# Sheet1.net
KiCad netlist of a schematic drawn in Altium Designer
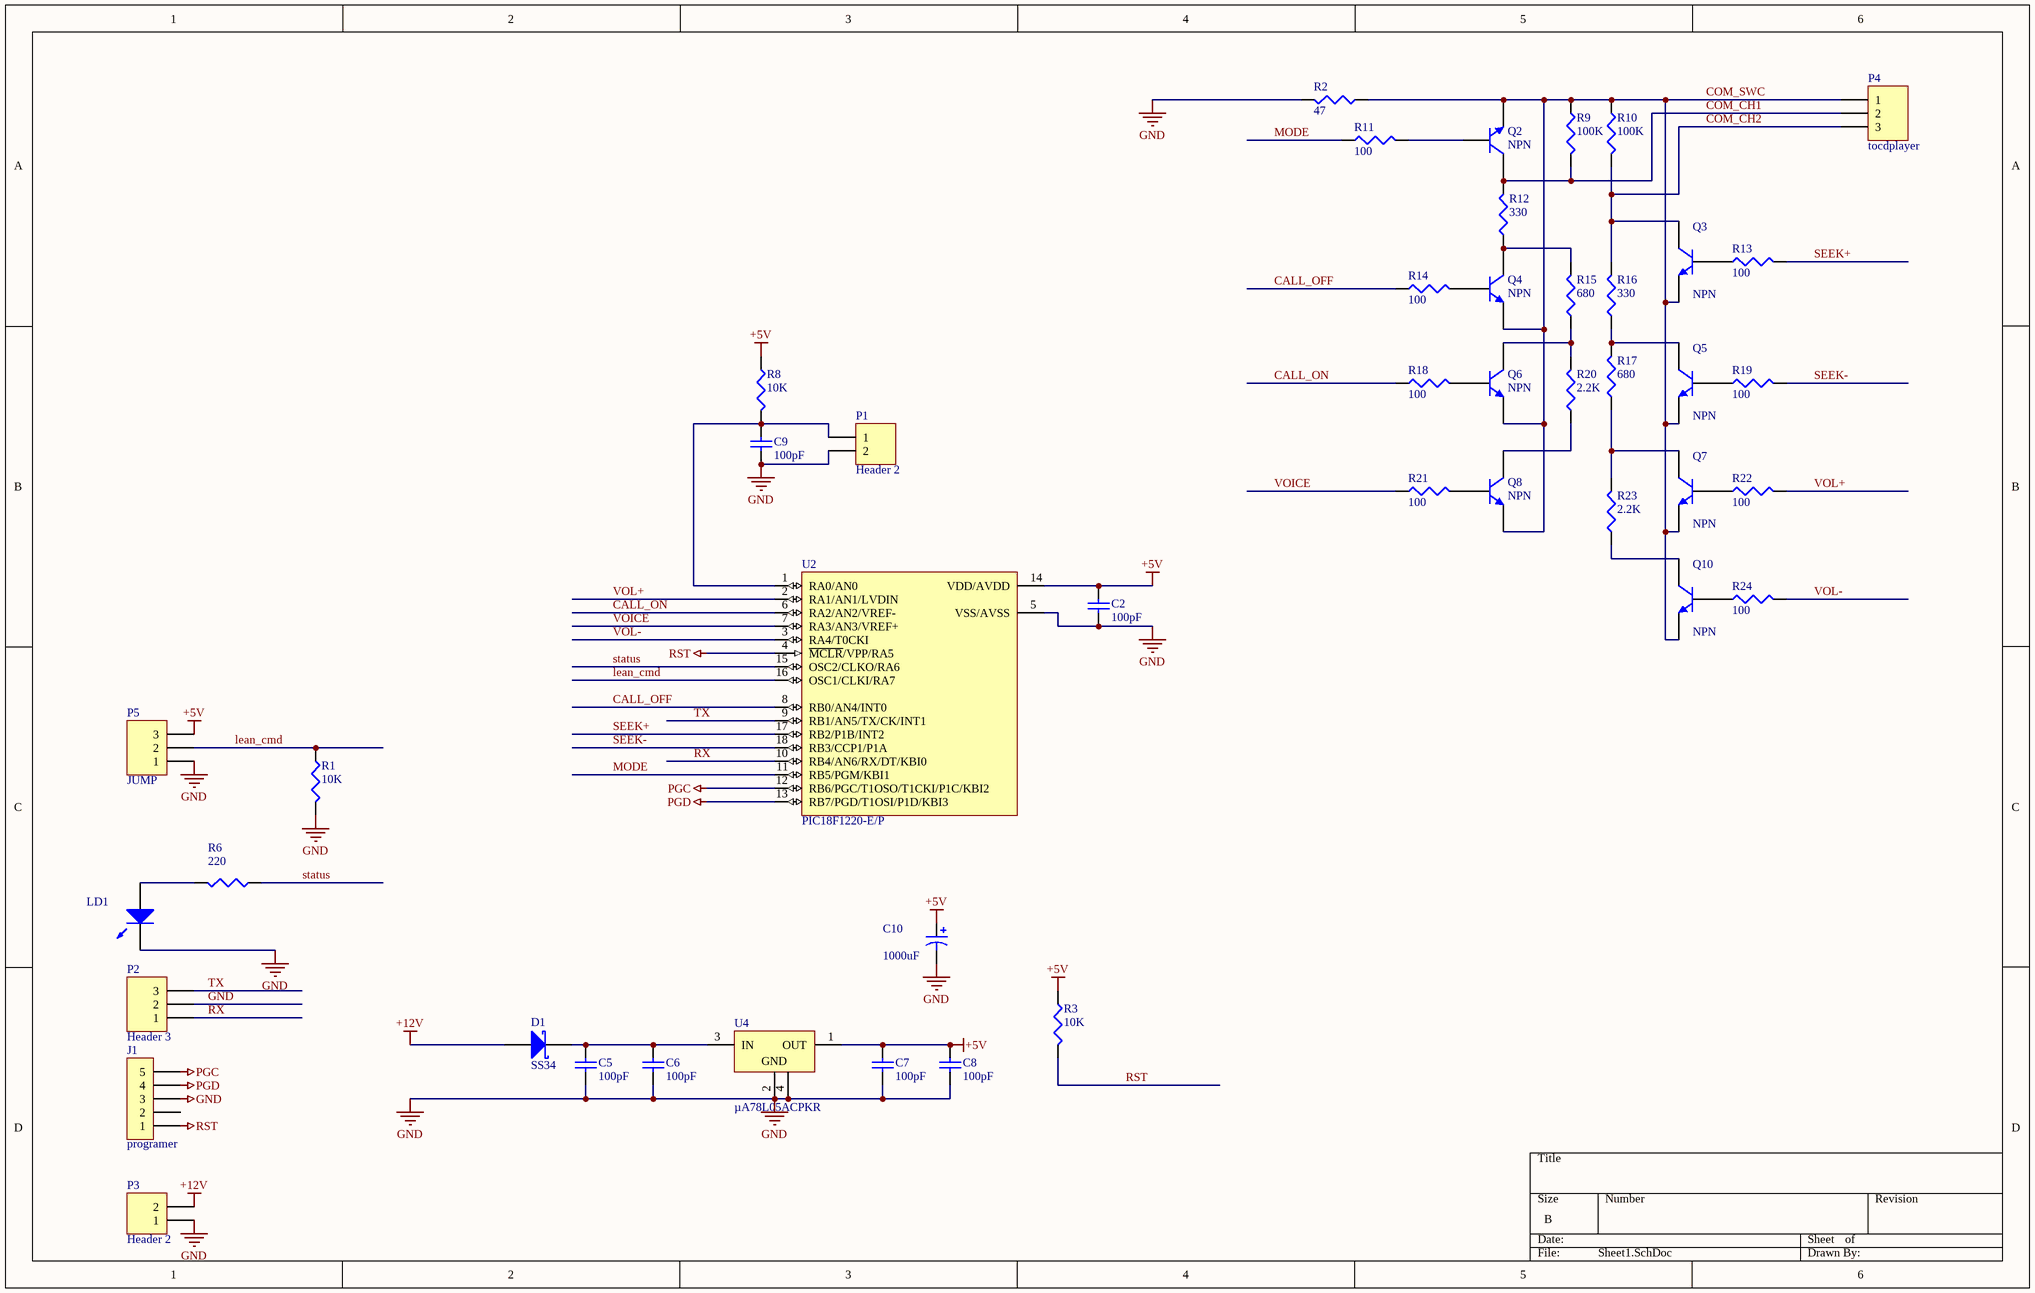
[diagram p0: Sheet1.SchDoc]

(export (version "E")
  (design (tool "Eeschema 10.0.6"))
  (components
    (comp (ref "C2")
      (value "100pF")
      (footprint "RESC2012L")
      (description "Capacitor (Semiconductor SIM Model)")
      (fields (field (name "Comment") "Cap Semi") (field (name "PUBLISHER") "Altium Limited"))
      (libsource (lib "Miscellaneous Devices") (part "Cap Semi"))
    )
    (comp (ref "C5")
      (value "100pF")
      (footprint "RESC2012L")
      (description "Capacitor (Semiconductor SIM Model)")
      (fields (field (name "Comment") "Cap Semi") (field (name "PUBLISHER") "Altium Limited"))
      (libsource (lib "Miscellaneous Devices") (part "Cap Semi"))
    )
    (comp (ref "C6")
      (value "100pF")
      (footprint "RESC2012L")
      (description "Capacitor (Semiconductor SIM Model)")
      (fields (field (name "Comment") "Cap Semi") (field (name "PUBLISHER") "Altium Limited"))
      (libsource (lib "Miscellaneous Devices") (part "Cap Semi"))
    )
    (comp (ref "C7")
      (value "100pF")
      (footprint "RESC2012L")
      (description "Capacitor (Semiconductor SIM Model)")
      (fields (field (name "Comment") "Cap Semi") (field (name "PUBLISHER") "Altium Limited"))
      (libsource (lib "Miscellaneous Devices") (part "Cap Semi"))
    )
    (comp (ref "C8")
      (value "100pF")
      (footprint "RESC2012L")
      (description "Capacitor (Semiconductor SIM Model)")
      (fields (field (name "Comment") "Cap Semi") (field (name "PUBLISHER") "Altium Limited"))
      (libsource (lib "Miscellaneous Devices") (part "Cap Semi"))
    )
    (comp (ref "C9")
      (value "100pF")
      (footprint "RESC2012L")
      (description "Capacitor (Semiconductor SIM Model)")
      (fields (field (name "Comment") "Cap Semi") (field (name "PUBLISHER") "Altium Limited"))
      (libsource (lib "Miscellaneous Devices") (part "Cap Semi"))
    )
    (comp (ref "C10")
      (value "1000uF")
      (footprint "CAP8x8")
      (description "CAP ALUM 1000UF 10V 20% SMD")
      (fields (field (name "Comment") "EEE-FT1A102AP") (field (name "PUBLISHER") "Altium Limited"))
      (libsource (lib "Miscellaneous Devices") (part "Cap Pol1"))
    )
    (comp (ref "D1")
      (value "SS34")
      (footprint "SMB")
      (description "DIODE SCHOTTKY 40V 3A SMC")
      (fields (field (name "PUBLISHER") "Altium Limited"))
      (libsource (lib "Schlib1") (part "D Schottky SS34"))
    )
    (comp (ref "J1")
      (value "programer")
      (footprint "HDR1x5")
      (description "Connector")
      (libsource (lib "*") (part "CON5"))
    )
    (comp (ref "LD1")
      (value "LNJ911W8BRU")
      (footprint "CD3216-1206")
      (description "LED BLUE THRU BOARD 1206")
      (libsource (lib "AM335X_ZCZ") (part "LEDRED1206"))
    )
    (comp (ref "P1")
      (value "Header 2")
      (footprint "CON_PLUG2")
      (description "Header, 2-Pin")
      (fields (field (name "PUBLISHER") "Altium Limited"))
      (libsource (lib "Miscellaneous Connectors") (part "Header 2"))
    )
    (comp (ref "P2")
      (value "Header 3")
      (footprint "HDR1X3")
      (description "Header, 3-Pin")
      (fields (field (name "PUBLISHER") "Altium Limited"))
      (libsource (lib "Miscellaneous Connectors") (part "Header 3"))
    )
    (comp (ref "P3")
      (value "Header 2")
      (footprint "HDR1X2")
      (description "Header, 2-Pin")
      (fields (field (name "PUBLISHER") "Altium Limited"))
      (libsource (lib "") (part "Header 2_1"))
    )
    (comp (ref "P4")
      (value "tocdplayer")
      (footprint "HDR1X3")
      (description "Header, 3-Pin")
      (fields (field (name "PUBLISHER") "Altium Limited"))
      (libsource (lib "") (part "Header 3_1"))
    )
    (comp (ref "P5")
      (value "JUMP")
      (footprint "HDR1X3")
      (description "Header, 3-Pin")
      (fields (field (name "PUBLISHER") "Altium Limited"))
      (libsource (lib "Miscellaneous Connectors") (part "Header 3"))
    )
    (comp (ref "Q2")
      (value "NPN")
      (footprint "SOT-23B")
      (description "NPN Bipolar Transistor")
      (fields (field (name "PUBLISHER") "Altium Limited"))
      (libsource (lib "Miscellaneous Devices") (part "NPN"))
    )
    (comp (ref "Q3")
      (value "NPN")
      (footprint "SOT-23B")
      (description "NPN Bipolar Transistor")
      (fields (field (name "PUBLISHER") "Altium Limited"))
      (libsource (lib "Miscellaneous Devices") (part "NPN"))
    )
    (comp (ref "Q4")
      (value "NPN")
      (footprint "SOT-23B")
      (description "NPN Bipolar Transistor")
      (fields (field (name "PUBLISHER") "Altium Limited"))
      (libsource (lib "Miscellaneous Devices") (part "NPN"))
    )
    (comp (ref "Q5")
      (value "NPN")
      (footprint "SOT-23B")
      (description "NPN Bipolar Transistor")
      (fields (field (name "PUBLISHER") "Altium Limited"))
      (libsource (lib "Miscellaneous Devices") (part "NPN"))
    )
    (comp (ref "Q6")
      (value "NPN")
      (footprint "SOT-23B")
      (description "NPN Bipolar Transistor")
      (fields (field (name "PUBLISHER") "Altium Limited"))
      (libsource (lib "Miscellaneous Devices") (part "NPN"))
    )
    (comp (ref "Q7")
      (value "NPN")
      (footprint "SOT-23B")
      (description "NPN Bipolar Transistor")
      (fields (field (name "PUBLISHER") "Altium Limited"))
      (libsource (lib "Miscellaneous Devices") (part "NPN"))
    )
    (comp (ref "Q8")
      (value "NPN")
      (footprint "SOT-23B")
      (description "NPN Bipolar Transistor")
      (fields (field (name "PUBLISHER") "Altium Limited"))
      (libsource (lib "Miscellaneous Devices") (part "NPN"))
    )
    (comp (ref "Q10")
      (value "NPN")
      (footprint "SOT-23B")
      (description "NPN Bipolar Transistor")
      (fields (field (name "PUBLISHER") "Altium Limited"))
      (libsource (lib "Miscellaneous Devices") (part "NPN"))
    )
    (comp (ref "R1")
      (value "10K")
      (footprint "RESC2012L")
      (description "Resistor")
      (fields (field (name "Comment") "Res3") (field (name "PUBLISHER") "Altium Limited"))
      (libsource (lib "Miscellaneous Devices") (part "Res3"))
    )
    (comp (ref "R2")
      (value "47")
      (footprint "RESC2012L")
      (description "Resistor")
      (fields (field (name "Comment") "Res3") (field (name "PUBLISHER") "Altium Limited"))
      (libsource (lib "Miscellaneous Devices") (part "Res3"))
    )
    (comp (ref "R3")
      (value "10K")
      (footprint "RESC2012L")
      (description "Resistor")
      (fields (field (name "Comment") "Res3") (field (name "PUBLISHER") "Altium Limited"))
      (libsource (lib "Miscellaneous Devices") (part "Res3"))
    )
    (comp (ref "R6")
      (value "220")
      (footprint "RESC2012L")
      (description "Resistor")
      (fields (field (name "Comment") "Res3") (field (name "PUBLISHER") "Altium Limited"))
      (libsource (lib "Miscellaneous Devices") (part "Res3"))
    )
    (comp (ref "R8")
      (value "10K")
      (footprint "RESC2012L")
      (description "Resistor")
      (fields (field (name "Comment") "Res3") (field (name "PUBLISHER") "Altium Limited"))
      (libsource (lib "Miscellaneous Devices") (part "Res3"))
    )
    (comp (ref "R9")
      (value "100K")
      (footprint "RESC2012L")
      (description "Resistor")
      (fields (field (name "Comment") "Res3") (field (name "PUBLISHER") "Altium Limited"))
      (libsource (lib "Miscellaneous Devices") (part "Res3"))
    )
    (comp (ref "R10")
      (value "100K")
      (footprint "RESC2012L")
      (description "Resistor")
      (fields (field (name "Comment") "Res3") (field (name "PUBLISHER") "Altium Limited"))
      (libsource (lib "Miscellaneous Devices") (part "Res3"))
    )
    (comp (ref "R11")
      (value "100")
      (footprint "RESC2012L")
      (description "Resistor")
      (fields (field (name "Comment") "Res3") (field (name "PUBLISHER") "Altium Limited"))
      (libsource (lib "Miscellaneous Devices") (part "Res3"))
    )
    (comp (ref "R12")
      (value "330")
      (footprint "RESC2012L")
      (description "Resistor")
      (fields (field (name "Comment") "Res3") (field (name "PUBLISHER") "Altium Limited"))
      (libsource (lib "Miscellaneous Devices") (part "Res3"))
    )
    (comp (ref "R13")
      (value "100")
      (footprint "RESC2012L")
      (description "Resistor")
      (fields (field (name "Comment") "Res3") (field (name "PUBLISHER") "Altium Limited"))
      (libsource (lib "Miscellaneous Devices") (part "Res3"))
    )
    (comp (ref "R14")
      (value "100")
      (footprint "RESC2012L")
      (description "Resistor")
      (fields (field (name "Comment") "Res3") (field (name "PUBLISHER") "Altium Limited"))
      (libsource (lib "Miscellaneous Devices") (part "Res3"))
    )
    (comp (ref "R15")
      (value "680")
      (footprint "RESC2012L")
      (description "Resistor")
      (fields (field (name "Comment") "Res3") (field (name "PUBLISHER") "Altium Limited"))
      (libsource (lib "Miscellaneous Devices") (part "Res3"))
    )
    (comp (ref "R16")
      (value "330")
      (footprint "RESC2012L")
      (description "Resistor")
      (fields (field (name "Comment") "Res3") (field (name "PUBLISHER") "Altium Limited"))
      (libsource (lib "Miscellaneous Devices") (part "Res3"))
    )
    (comp (ref "R17")
      (value "680")
      (footprint "RESC2012L")
      (description "Resistor")
      (fields (field (name "Comment") "Res3") (field (name "PUBLISHER") "Altium Limited"))
      (libsource (lib "Miscellaneous Devices") (part "Res3"))
    )
    (comp (ref "R18")
      (value "100")
      (footprint "RESC2012L")
      (description "Resistor")
      (fields (field (name "Comment") "Res3") (field (name "PUBLISHER") "Altium Limited"))
      (libsource (lib "Miscellaneous Devices") (part "Res3"))
    )
    (comp (ref "R19")
      (value "100")
      (footprint "RESC2012L")
      (description "Resistor")
      (fields (field (name "Comment") "Res3") (field (name "PUBLISHER") "Altium Limited"))
      (libsource (lib "Miscellaneous Devices") (part "Res3"))
    )
    (comp (ref "R20")
      (value "2.2K")
      (footprint "RESC2012L")
      (description "Resistor")
      (fields (field (name "Comment") "Res3") (field (name "PUBLISHER") "Altium Limited"))
      (libsource (lib "Miscellaneous Devices") (part "Res3"))
    )
    (comp (ref "R21")
      (value "100")
      (footprint "RESC2012L")
      (description "Resistor")
      (fields (field (name "Comment") "Res3") (field (name "PUBLISHER") "Altium Limited"))
      (libsource (lib "Miscellaneous Devices") (part "Res3"))
    )
    (comp (ref "R22")
      (value "100")
      (footprint "RESC2012L")
      (description "Resistor")
      (fields (field (name "Comment") "Res3") (field (name "PUBLISHER") "Altium Limited"))
      (libsource (lib "Miscellaneous Devices") (part "Res3"))
    )
    (comp (ref "R23")
      (value "2.2K")
      (footprint "RESC2012L")
      (description "Resistor")
      (fields (field (name "Comment") "Res3") (field (name "PUBLISHER") "Altium Limited"))
      (libsource (lib "Miscellaneous Devices") (part "Res3"))
    )
    (comp (ref "R24")
      (value "100")
      (footprint "RESC2012L")
      (description "Resistor")
      (fields (field (name "Comment") "Res3") (field (name "PUBLISHER") "Altium Limited"))
      (libsource (lib "Miscellaneous Devices") (part "Res3"))
    )
    (comp (ref "U2")
      (value "PIC18F1220-E/P")
      (footprint "PDIP300-P18")
      (fields (field (name "PUBLISHER") "Altium Limited"))
      (libsource (lib "Microchip Microcontroller 8-Bit PIC18") (part "PIC18F1220-E/P"))
    )
    (comp (ref "U4")
      (value "µA78L05ACPKR")
      (footprint "PK03")
      (description "Positive-Voltage Regulator")
      (fields (field (name "PUBLISHER") "Altium Limited"))
      (libsource (lib "Schlib1") (part "µA78L05ACPKR"))
    )
  )
  (nets
    (net (code "1") (name "+5V") (class "Default")
      (node (ref "C10") (pin "1") (pinfunction "1_1") (pintype "passive"))
      (node (ref "C2") (pin "2") (pinfunction "2_2") (pintype "passive"))
      (node (ref "C7") (pin "2") (pinfunction "2_2") (pintype "passive"))
      (node (ref "C8") (pin "2") (pinfunction "2_2") (pintype "passive"))
      (node (ref "P5") (pin "3") (pinfunction "3_3") (pintype "passive"))
      (node (ref "R3") (pin "1") (pinfunction "1_1") (pintype "passive"))
      (node (ref "R8") (pin "1") (pinfunction "1_1") (pintype "passive"))
      (node (ref "U2") (pin "14") (pinfunction "VDD/AVDD_14") (pintype "power_in"))
      (node (ref "U4") (pin "1") (pinfunction "OUT_1") (pintype "power_in"))
    )
    (net (code "2") (name "+12V") (class "Default")
      (node (ref "D1") (pin "1") (pinfunction "A_1") (pintype "passive"))
      (node (ref "P3") (pin "2") (pinfunction "2_2") (pintype "passive"))
    )
    (net (code "3") (name "/CALL_OFF") (class "Default")
      (node (ref "R14") (pin "1") (pinfunction "1_1") (pintype "passive"))
      (node (ref "U2") (pin "8") (pinfunction "RB0/AN4/INT0_8") (pintype "bidirectional"))
    )
    (net (code "4") (name "/CALL_ON") (class "Default")
      (node (ref "R18") (pin "1") (pinfunction "1_1") (pintype "passive"))
      (node (ref "U2") (pin "6") (pinfunction "RA2/AN2/VREF-_6") (pintype "bidirectional"))
    )
    (net (code "5") (name "/COM_CH1") (class "Default")
      (node (ref "P4") (pin "2") (pinfunction "2_2") (pintype "passive"))
      (node (ref "Q2") (pin "1") (pinfunction "C_1") (pintype "passive"))
      (node (ref "R12") (pin "2") (pinfunction "2_2") (pintype "passive"))
      (node (ref "R9") (pin "2") (pinfunction "2_2") (pintype "passive"))
    )
    (net (code "6") (name "/COM_CH2") (class "Default")
      (node (ref "P4") (pin "3") (pinfunction "3_3") (pintype "passive"))
      (node (ref "Q3") (pin "1") (pinfunction "C_1") (pintype "passive"))
      (node (ref "R10") (pin "2") (pinfunction "2_2") (pintype "passive"))
      (node (ref "R16") (pin "2") (pinfunction "2_2") (pintype "passive"))
    )
    (net (code "7") (name "/COM_SWC") (class "Default")
      (node (ref "P4") (pin "1") (pinfunction "1_1") (pintype "passive"))
      (node (ref "Q10") (pin "3") (pinfunction "E_3") (pintype "passive"))
      (node (ref "Q2") (pin "3") (pinfunction "E_3") (pintype "passive"))
      (node (ref "Q3") (pin "3") (pinfunction "E_3") (pintype "passive"))
      (node (ref "Q4") (pin "3") (pinfunction "E_3") (pintype "passive"))
      (node (ref "Q5") (pin "3") (pinfunction "E_3") (pintype "passive"))
      (node (ref "Q6") (pin "3") (pinfunction "E_3") (pintype "passive"))
      (node (ref "Q7") (pin "3") (pinfunction "E_3") (pintype "passive"))
      (node (ref "Q8") (pin "3") (pinfunction "E_3") (pintype "passive"))
      (node (ref "R10") (pin "1") (pinfunction "1_1") (pintype "passive"))
      (node (ref "R2") (pin "1") (pinfunction "1_1") (pintype "passive"))
      (node (ref "R9") (pin "1") (pinfunction "1_1") (pintype "passive"))
    )
    (net (code "8") (name "/MODE") (class "Default")
      (node (ref "R11") (pin "1") (pinfunction "1_1") (pintype "passive"))
      (node (ref "U2") (pin "11") (pinfunction "RB5/PGM/KBI1_11") (pintype "bidirectional"))
    )
    (net (code "9") (name "/RX") (class "Default")
      (node (ref "P2") (pin "1") (pinfunction "1_1") (pintype "passive"))
      (node (ref "U2") (pin "10") (pinfunction "RB4/AN6/RX/DT/KBI0_10") (pintype "bidirectional"))
    )
    (net (code "10") (name "/SEEK+") (class "Default")
      (node (ref "R13") (pin "2") (pinfunction "2_2") (pintype "passive"))
      (node (ref "U2") (pin "17") (pinfunction "RB2/P1B/INT2_17") (pintype "bidirectional"))
    )
    (net (code "11") (name "/SEEK-") (class "Default")
      (node (ref "R19") (pin "2") (pinfunction "2_2") (pintype "passive"))
      (node (ref "U2") (pin "18") (pinfunction "RB3/CCP1/P1A_18") (pintype "bidirectional"))
    )
    (net (code "12") (name "/TX") (class "Default")
      (node (ref "P2") (pin "3") (pinfunction "3_3") (pintype "passive"))
      (node (ref "U2") (pin "9") (pinfunction "RB1/AN5/TX/CK/INT1_9") (pintype "bidirectional"))
    )
    (net (code "13") (name "/VOICE") (class "Default")
      (node (ref "R21") (pin "1") (pinfunction "1_1") (pintype "passive"))
      (node (ref "U2") (pin "7") (pinfunction "RA3/AN3/VREF+_7") (pintype "bidirectional"))
    )
    (net (code "14") (name "/VOL+") (class "Default")
      (node (ref "R22") (pin "2") (pinfunction "2_2") (pintype "passive"))
      (node (ref "U2") (pin "2") (pinfunction "RA1/AN1/LVDIN_2") (pintype "bidirectional"))
    )
    (net (code "15") (name "/VOL-") (class "Default")
      (node (ref "R24") (pin "2") (pinfunction "2_2") (pintype "passive"))
      (node (ref "U2") (pin "3") (pinfunction "RA4/T0CKI_3") (pintype "bidirectional"))
    )
    (net (code "16") (name "/lean_cmd") (class "Default")
      (node (ref "P5") (pin "2") (pinfunction "2_2") (pintype "passive"))
      (node (ref "R1") (pin "1") (pinfunction "1_1") (pintype "passive"))
      (node (ref "U2") (pin "16") (pinfunction "OSC1/CLKI/RA7_16") (pintype "bidirectional"))
    )
    (net (code "17") (name "/status") (class "Default")
      (node (ref "R6") (pin "1") (pinfunction "1_1") (pintype "passive"))
      (node (ref "U2") (pin "15") (pinfunction "OSC2/CLKO/RA6_15") (pintype "bidirectional"))
    )
    (net (code "18") (name "GND") (class "Default")
      (node (ref "C10") (pin "2") (pinfunction "2_2") (pintype "passive"))
      (node (ref "C2") (pin "1") (pinfunction "1_1") (pintype "passive"))
      (node (ref "C5") (pin "1") (pinfunction "1_1") (pintype "passive"))
      (node (ref "C6") (pin "1") (pinfunction "1_1") (pintype "passive"))
      (node (ref "C7") (pin "1") (pinfunction "1_1") (pintype "passive"))
      (node (ref "C8") (pin "1") (pinfunction "1_1") (pintype "passive"))
      (node (ref "C9") (pin "1") (pinfunction "1_1") (pintype "passive"))
      (node (ref "J1") (pin "3") (pinfunction "3_3") (pintype "passive"))
      (node (ref "LD1") (pin "2") (pinfunction "K_2") (pintype "passive"))
      (node (ref "P1") (pin "2") (pinfunction "2_2") (pintype "passive"))
      (node (ref "P2") (pin "2") (pinfunction "2_2") (pintype "passive"))
      (node (ref "P3") (pin "1") (pinfunction "1_1") (pintype "passive"))
      (node (ref "P5") (pin "1") (pinfunction "1_1") (pintype "passive"))
      (node (ref "R1") (pin "2") (pinfunction "2_2") (pintype "passive"))
      (node (ref "R2") (pin "2") (pinfunction "2_2") (pintype "passive"))
      (node (ref "U2") (pin "5") (pinfunction "VSS/AVSS_5") (pintype "power_in"))
      (node (ref "U4") (pin "2") (pinfunction "GND_2") (pintype "power_in"))
      (node (ref "U4") (pin "4") (pinfunction "GND_4") (pintype "power_in"))
    )
    (net (code "19") (name "Net-(D1-K)") (class "Default")
      (node (ref "C5") (pin "2") (pinfunction "2_2") (pintype "passive"))
      (node (ref "C6") (pin "2") (pinfunction "2_2") (pintype "passive"))
      (node (ref "D1") (pin "2") (pinfunction "K_2") (pintype "passive"))
      (node (ref "U4") (pin "3") (pinfunction "IN_3") (pintype "power_in"))
    )
    (net (code "20") (name "Net-(LD1-A)") (class "Default")
      (node (ref "LD1") (pin "1") (pinfunction "A_1") (pintype "passive"))
      (node (ref "R6") (pin "2") (pinfunction "2_2") (pintype "passive"))
    )
    (net (code "21") (name "Net-(Q2-B)") (class "Default")
      (node (ref "Q2") (pin "2") (pinfunction "B_2") (pintype "passive"))
      (node (ref "R11") (pin "2") (pinfunction "2_2") (pintype "passive"))
    )
    (net (code "22") (name "Net-(Q3-B)") (class "Default")
      (node (ref "Q3") (pin "2") (pinfunction "B_2") (pintype "passive"))
      (node (ref "R13") (pin "1") (pinfunction "1_1") (pintype "passive"))
    )
    (net (code "23") (name "Net-(Q4-B)") (class "Default")
      (node (ref "Q4") (pin "2") (pinfunction "B_2") (pintype "passive"))
      (node (ref "R14") (pin "2") (pinfunction "2_2") (pintype "passive"))
    )
    (net (code "24") (name "Net-(Q4-C)") (class "Default")
      (node (ref "Q4") (pin "1") (pinfunction "C_1") (pintype "passive"))
      (node (ref "R12") (pin "1") (pinfunction "1_1") (pintype "passive"))
      (node (ref "R15") (pin "2") (pinfunction "2_2") (pintype "passive"))
    )
    (net (code "25") (name "Net-(Q5-B)") (class "Default")
      (node (ref "Q5") (pin "2") (pinfunction "B_2") (pintype "passive"))
      (node (ref "R19") (pin "1") (pinfunction "1_1") (pintype "passive"))
    )
    (net (code "26") (name "Net-(Q5-C)") (class "Default")
      (node (ref "Q5") (pin "1") (pinfunction "C_1") (pintype "passive"))
      (node (ref "R16") (pin "1") (pinfunction "1_1") (pintype "passive"))
      (node (ref "R17") (pin "2") (pinfunction "2_2") (pintype "passive"))
    )
    (net (code "27") (name "Net-(Q6-B)") (class "Default")
      (node (ref "Q6") (pin "2") (pinfunction "B_2") (pintype "passive"))
      (node (ref "R18") (pin "2") (pinfunction "2_2") (pintype "passive"))
    )
    (net (code "28") (name "Net-(Q6-C)") (class "Default")
      (node (ref "Q6") (pin "1") (pinfunction "C_1") (pintype "passive"))
      (node (ref "R15") (pin "1") (pinfunction "1_1") (pintype "passive"))
      (node (ref "R20") (pin "2") (pinfunction "2_2") (pintype "passive"))
    )
    (net (code "29") (name "Net-(Q7-B)") (class "Default")
      (node (ref "Q7") (pin "2") (pinfunction "B_2") (pintype "passive"))
      (node (ref "R22") (pin "1") (pinfunction "1_1") (pintype "passive"))
    )
    (net (code "30") (name "Net-(Q7-C)") (class "Default")
      (node (ref "Q7") (pin "1") (pinfunction "C_1") (pintype "passive"))
      (node (ref "R17") (pin "1") (pinfunction "1_1") (pintype "passive"))
      (node (ref "R23") (pin "2") (pinfunction "2_2") (pintype "passive"))
    )
    (net (code "31") (name "Net-(Q8-B)") (class "Default")
      (node (ref "Q8") (pin "2") (pinfunction "B_2") (pintype "passive"))
      (node (ref "R21") (pin "2") (pinfunction "2_2") (pintype "passive"))
    )
    (net (code "32") (name "Net-(Q8-C)") (class "Default")
      (node (ref "Q8") (pin "1") (pinfunction "C_1") (pintype "passive"))
      (node (ref "R20") (pin "1") (pinfunction "1_1") (pintype "passive"))
    )
    (net (code "33") (name "Net-(Q10-B)") (class "Default")
      (node (ref "Q10") (pin "2") (pinfunction "B_2") (pintype "passive"))
      (node (ref "R24") (pin "1") (pinfunction "1_1") (pintype "passive"))
    )
    (net (code "34") (name "Net-(Q10-C)") (class "Default")
      (node (ref "Q10") (pin "1") (pinfunction "C_1") (pintype "passive"))
      (node (ref "R23") (pin "1") (pinfunction "1_1") (pintype "passive"))
    )
    (net (code "35") (name "Net-(U2-RA0{slash}AN0)") (class "Default")
      (node (ref "C9") (pin "2") (pinfunction "2_2") (pintype "passive"))
      (node (ref "P1") (pin "1") (pinfunction "1_1") (pintype "passive"))
      (node (ref "R8") (pin "2") (pinfunction "2_2") (pintype "passive"))
      (node (ref "U2") (pin "1") (pinfunction "RA0/AN0_1") (pintype "bidirectional"))
    )
    (net (code "36") (name "PGC") (class "Default")
      (node (ref "J1") (pin "5") (pinfunction "5_5") (pintype "passive"))
      (node (ref "U2") (pin "12") (pinfunction "RB6/PGC/T1OSO/T1CKI/P1C/KBI2_12") (pintype "bidirectional"))
    )
    (net (code "37") (name "PGD") (class "Default")
      (node (ref "J1") (pin "4") (pinfunction "4_4") (pintype "passive"))
      (node (ref "U2") (pin "13") (pinfunction "RB7/PGD/T1OSI/P1D/KBI3_13") (pintype "bidirectional"))
    )
    (net (code "38") (name "RST") (class "Default")
      (node (ref "J1") (pin "1") (pinfunction "1_1") (pintype "passive"))
      (node (ref "R3") (pin "2") (pinfunction "2_2") (pintype "passive"))
      (node (ref "U2") (pin "4") (pinfunction "~{MCLR}/VPP/RA5_4") (pintype "input"))
    )
    (net (code "39") (name "unconnected-(J1-Pad2)") (class "Default")
      (node (ref "J1") (pin "2") (pinfunction "2_2") (pintype "passive"))
    )
  )
)
